# display.net
KiCad netlist of a schematic drawn in EAGLE
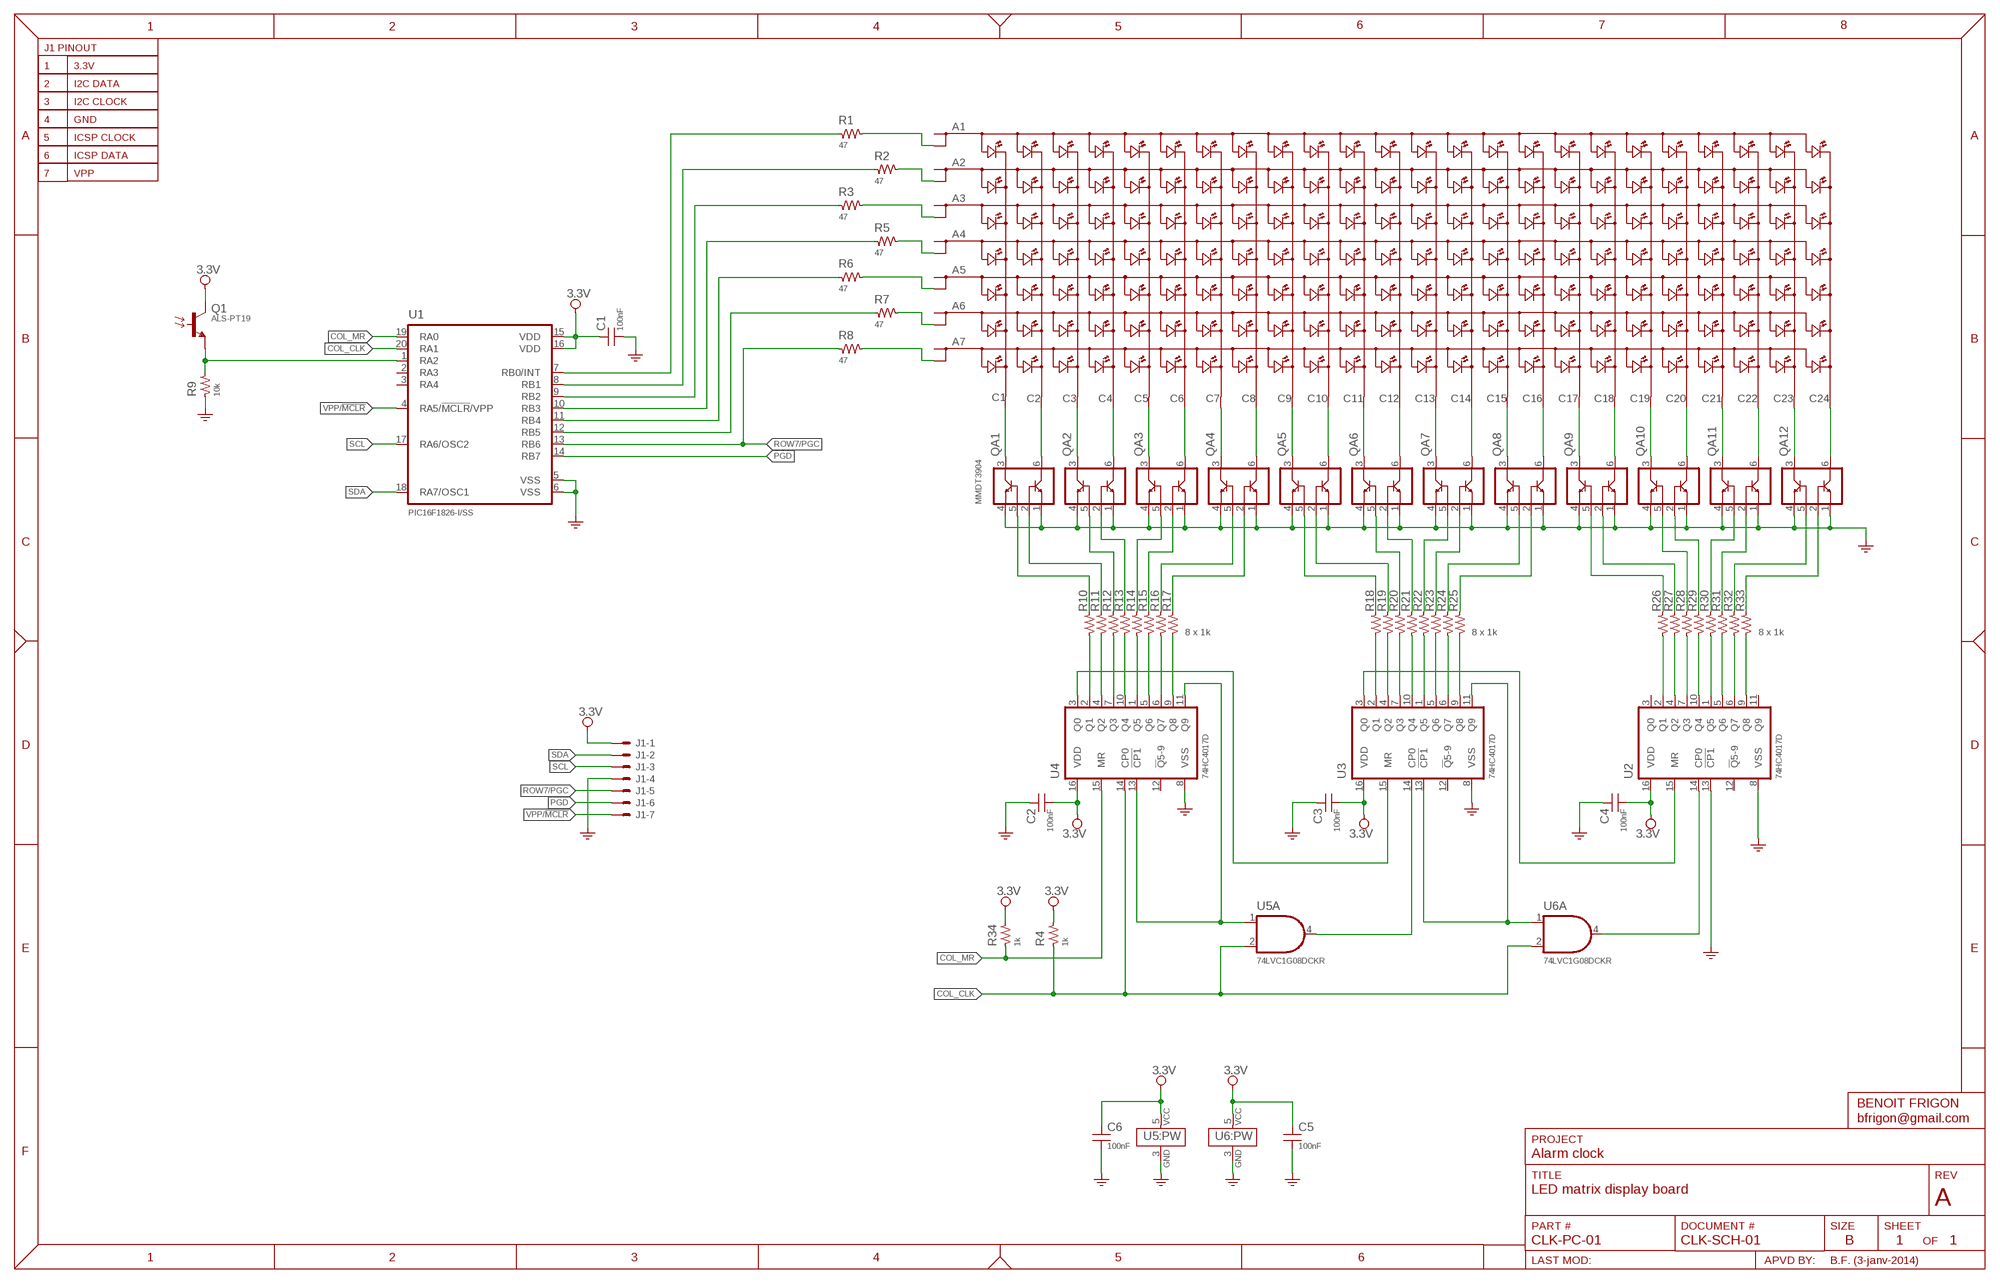
[diagram p0: schematic, sheet 1]

(export (version "E")
  (design (tool "Eeschema 10.0.6"))
  (components
    (comp (ref "C1")
      (value "100nF")
      (footprint "eagle-import:SMD_0603")
      (fields (field (name "PRICE") "0.00"))
      (libsource (lib "eagle-import") (part "CAP-0603"))
    )
    (comp (ref "C2")
      (value "100nF")
      (footprint "eagle-import:SMD_0603")
      (fields (field (name "PRICE") "0.00"))
      (libsource (lib "eagle-import") (part "CAP-0603"))
    )
    (comp (ref "C3")
      (value "100nF")
      (footprint "eagle-import:SMD_0603")
      (description "{DESCRIPTION} - SMT 0603 - {value}")
      (fields (field (name "PACKAGE") "SMT 0603") (field (name "PRICE") "0.00"))
      (libsource (lib "eagle-import") (part "CAP-0603"))
    )
    (comp (ref "C4")
      (value "100nF")
      (footprint "eagle-import:SMD_0603")
      (description "{DESCRIPTION} - SMT 0603 - {value}")
      (fields (field (name "PACKAGE") "SMT 0603") (field (name "PRICE") "0.00"))
      (libsource (lib "eagle-import") (part "CAP-0603"))
    )
    (comp (ref "C5")
      (value "100nF")
      (footprint "eagle-import:SMD_0603")
      (libsource (lib "eagle-import") (part "CAP-0603"))
    )
    (comp (ref "C6")
      (value "100nF")
      (footprint "eagle-import:SMD_0603")
      (libsource (lib "eagle-import") (part "CAP-0603"))
    )
    (comp (ref "J1")
      (value "SNG-2MM-HEADER-07-V")
      (footprint "eagle-import:DF3X-7P-2DSA")
      (fields
        (field (name "MFG") "Hirose Electronic")
        (field (name "PART_NO") "DF3A-7P-2DSA")
        (field (name "PRICE") "0.37")
        (field (name "SKU") "H2099-ND")
        (field (name "SUPPLIER") "Digi-Key")
      )
      (libsource (lib "eagle-import") (part "SNG-2MM-HEADER-07-V"))
    )
    (comp (ref "Q1")
      (value "ALS-PT19")
      (footprint "eagle-import:ALS-PT19")
      (fields
        (field (name "MFG") "Everlight")
        (field (name "PART_NO") "ALS-PT19-315C/L177/TR8")
        (field (name "PART_NO_1") "ALS-PT19-315C/L177/TR8")
      )
      (libsource (lib "eagle-import") (part "ALS-PT19"))
    )
    (comp (ref "QA1")
      (value "MMDT3904")
      (footprint "eagle-import:SOT363")
      (fields (field (name "MFG") "Diodes Inc."))
      (libsource (lib "eagle-import") (part "MMDT3904"))
    )
    (comp (ref "QA2")
      (value "MMDT3904")
      (footprint "eagle-import:SOT363")
      (fields (field (name "MFG") "Diodes Inc."))
      (libsource (lib "eagle-import") (part "MMDT3904"))
    )
    (comp (ref "QA3")
      (value "MMDT3904")
      (footprint "eagle-import:SOT363")
      (fields (field (name "MFG") "Diodes Inc."))
      (libsource (lib "eagle-import") (part "MMDT3904"))
    )
    (comp (ref "QA4")
      (value "MMDT3904")
      (footprint "eagle-import:SOT363")
      (fields (field (name "MFG") "Diodes Inc."))
      (libsource (lib "eagle-import") (part "MMDT3904"))
    )
    (comp (ref "QA5")
      (value "MMDT3904")
      (footprint "eagle-import:SOT363")
      (fields (field (name "MFG") "Diodes Inc."))
      (libsource (lib "eagle-import") (part "MMDT3904"))
    )
    (comp (ref "QA6")
      (value "MMDT3904")
      (footprint "eagle-import:SOT363")
      (fields (field (name "MFG") "Diodes Inc."))
      (libsource (lib "eagle-import") (part "MMDT3904"))
    )
    (comp (ref "QA7")
      (value "MMDT3904")
      (footprint "eagle-import:SOT363")
      (fields (field (name "MFG") "Diodes Inc."))
      (libsource (lib "eagle-import") (part "MMDT3904"))
    )
    (comp (ref "QA8")
      (value "MMDT3904")
      (footprint "eagle-import:SOT363")
      (fields (field (name "MFG") "Diodes Inc."))
      (libsource (lib "eagle-import") (part "MMDT3904"))
    )
    (comp (ref "QA9")
      (value "MMDT3904")
      (footprint "eagle-import:SOT363")
      (fields (field (name "MFG") "Diodes Inc."))
      (libsource (lib "eagle-import") (part "MMDT3904"))
    )
    (comp (ref "QA10")
      (value "MMDT3904")
      (footprint "eagle-import:SOT363")
      (fields (field (name "MFG") "Diodes Inc."))
      (libsource (lib "eagle-import") (part "MMDT3904"))
    )
    (comp (ref "QA11")
      (value "MMDT3904")
      (footprint "eagle-import:SOT363")
      (fields (field (name "MFG") "Diodes Inc."))
      (libsource (lib "eagle-import") (part "MMDT3904"))
    )
    (comp (ref "QA12")
      (value "MMDT3904")
      (footprint "eagle-import:SOT363")
      (fields (field (name "MFG") "Diodes Inc."))
      (libsource (lib "eagle-import") (part "MMDT3904"))
    )
    (comp (ref "R1")
      (value "47")
      (footprint "eagle-import:SMD_0603")
      (description "{DESCRIPTION} - SMT 0603 - {VALUE}")
      (fields (field (name "PACKAGE") "SMT 0603") (field (name "PRICE") "0.00"))
      (libsource (lib "eagle-import") (part "RES-0603"))
    )
    (comp (ref "R2")
      (value "47")
      (footprint "eagle-import:SMD_0603")
      (description "{DESCRIPTION} - SMT 0603 - {VALUE}")
      (fields (field (name "PACKAGE") "SMT 0603") (field (name "PRICE") "0.00"))
      (libsource (lib "eagle-import") (part "RES-0603"))
    )
    (comp (ref "R3")
      (value "47")
      (footprint "eagle-import:SMD_0603")
      (description "{DESCRIPTION} - SMT 0603 - {VALUE}")
      (fields (field (name "PACKAGE") "SMT 0603") (field (name "PRICE") "0.00"))
      (libsource (lib "eagle-import") (part "RES-0603"))
    )
    (comp (ref "R4")
      (value "1k")
      (footprint "eagle-import:SMD_0603")
      (fields (field (name "PRICE") "0.00"))
      (libsource (lib "eagle-import") (part "RES-0603"))
    )
    (comp (ref "R5")
      (value "47")
      (footprint "eagle-import:SMD_0603")
      (description "{DESCRIPTION} - SMT 0603 - {VALUE}")
      (fields (field (name "PACKAGE") "SMT 0603") (field (name "PRICE") "0.00"))
      (libsource (lib "eagle-import") (part "RES-0603"))
    )
    (comp (ref "R6")
      (value "47")
      (footprint "eagle-import:SMD_0603")
      (description "{DESCRIPTION} - SMT 0603 - {VALUE}")
      (fields (field (name "PACKAGE") "SMT 0603") (field (name "PRICE") "0.00"))
      (libsource (lib "eagle-import") (part "RES-0603"))
    )
    (comp (ref "R7")
      (value "47")
      (footprint "eagle-import:SMD_0603")
      (description "{DESCRIPTION} - SMT 0603 - {VALUE}")
      (fields (field (name "PACKAGE") "SMT 0603") (field (name "PRICE") "0.00"))
      (libsource (lib "eagle-import") (part "RES-0603"))
    )
    (comp (ref "R8")
      (value "47")
      (footprint "eagle-import:SMD_0603")
      (description "{DESCRIPTION} - SMT 0603 - {VALUE}")
      (fields (field (name "PACKAGE") "SMT 0603") (field (name "PRICE") "0.00"))
      (libsource (lib "eagle-import") (part "RES-0603"))
    )
    (comp (ref "R9")
      (value "10k")
      (footprint "eagle-import:SMD_0603")
      (libsource (lib "eagle-import") (part "RES-0603"))
    )
    (comp (ref "R10")
      (value "1k")
      (footprint "eagle-import:SMD_0603")
      (fields (field (name "PRICE") "0.00"))
      (libsource (lib "eagle-import") (part "RES-0603"))
    )
    (comp (ref "R11")
      (value "1k")
      (footprint "eagle-import:SMD_0603")
      (description "{DESCRIPTION} - SMT 0603 - {VALUE}")
      (fields (field (name "PACKAGE") "SMT 0603") (field (name "PRICE") "0.00"))
      (libsource (lib "eagle-import") (part "RES-0603"))
    )
    (comp (ref "R12")
      (value "1k")
      (footprint "eagle-import:SMD_0603")
      (description "{DESCRIPTION} - SMT 0603 - {VALUE}")
      (fields (field (name "PACKAGE") "SMT 0603") (field (name "PRICE") "0.00"))
      (libsource (lib "eagle-import") (part "RES-0603"))
    )
    (comp (ref "R13")
      (value "1k")
      (footprint "eagle-import:SMD_0603")
      (description "{DESCRIPTION} - SMT 0603 - {VALUE}")
      (fields (field (name "PACKAGE") "SMT 0603") (field (name "PRICE") "0.00"))
      (libsource (lib "eagle-import") (part "RES-0603"))
    )
    (comp (ref "R14")
      (value "1k")
      (footprint "eagle-import:SMD_0603")
      (description "{DESCRIPTION} - SMT 0603 - {VALUE}")
      (fields (field (name "PACKAGE") "SMT 0603") (field (name "PRICE") "0.00"))
      (libsource (lib "eagle-import") (part "RES-0603"))
    )
    (comp (ref "R15")
      (value "1k")
      (footprint "eagle-import:SMD_0603")
      (description "{DESCRIPTION} - SMT 0603 - {VALUE}")
      (fields (field (name "PACKAGE") "SMT 0603") (field (name "PRICE") "0.00"))
      (libsource (lib "eagle-import") (part "RES-0603"))
    )
    (comp (ref "R16")
      (value "1k")
      (footprint "eagle-import:SMD_0603")
      (description "{DESCRIPTION} - SMT 0603 - {VALUE}")
      (fields (field (name "PACKAGE") "SMT 0603") (field (name "PRICE") "0.00"))
      (libsource (lib "eagle-import") (part "RES-0603"))
    )
    (comp (ref "R17")
      (value "1k")
      (footprint "eagle-import:SMD_0603")
      (description "{DESCRIPTION} - SMT 0603 - {VALUE}")
      (fields (field (name "PACKAGE") "SMT 0603") (field (name "PRICE") "0.00"))
      (libsource (lib "eagle-import") (part "RES-0603"))
    )
    (comp (ref "R18")
      (value "1k")
      (footprint "eagle-import:SMD_0603")
      (description "{DESCRIPTION} - SMT 0603 - {VALUE}")
      (fields (field (name "PACKAGE") "SMT 0603") (field (name "PRICE") "0.00"))
      (libsource (lib "eagle-import") (part "RES-0603"))
    )
    (comp (ref "R19")
      (value "1k")
      (footprint "eagle-import:SMD_0603")
      (description "{DESCRIPTION} - SMT 0603 - {VALUE}")
      (fields (field (name "PACKAGE") "SMT 0603") (field (name "PRICE") "0.00"))
      (libsource (lib "eagle-import") (part "RES-0603"))
    )
    (comp (ref "R20")
      (value "1k")
      (footprint "eagle-import:SMD_0603")
      (description "{DESCRIPTION} - SMT 0603 - {VALUE}")
      (fields (field (name "PACKAGE") "SMT 0603") (field (name "PRICE") "0.00"))
      (libsource (lib "eagle-import") (part "RES-0603"))
    )
    (comp (ref "R21")
      (value "1k")
      (footprint "eagle-import:SMD_0603")
      (description "{DESCRIPTION} - SMT 0603 - {VALUE}")
      (fields (field (name "PACKAGE") "SMT 0603") (field (name "PRICE") "0.00"))
      (libsource (lib "eagle-import") (part "RES-0603"))
    )
    (comp (ref "R22")
      (value "1k")
      (footprint "eagle-import:SMD_0603")
      (description "{DESCRIPTION} - SMT 0603 - {VALUE}")
      (fields (field (name "PACKAGE") "SMT 0603") (field (name "PRICE") "0.00"))
      (libsource (lib "eagle-import") (part "RES-0603"))
    )
    (comp (ref "R23")
      (value "1k")
      (footprint "eagle-import:SMD_0603")
      (description "{DESCRIPTION} - SMT 0603 - {VALUE}")
      (fields (field (name "PACKAGE") "SMT 0603") (field (name "PRICE") "0.00"))
      (libsource (lib "eagle-import") (part "RES-0603"))
    )
    (comp (ref "R24")
      (value "1k")
      (footprint "eagle-import:SMD_0603")
      (description "{DESCRIPTION} - SMT 0603 - {VALUE}")
      (fields (field (name "PACKAGE") "SMT 0603") (field (name "PRICE") "0.00"))
      (libsource (lib "eagle-import") (part "RES-0603"))
    )
    (comp (ref "R25")
      (value "1k")
      (footprint "eagle-import:SMD_0603")
      (description "{DESCRIPTION} - SMT 0603 - {VALUE}")
      (fields (field (name "PACKAGE") "SMT 0603") (field (name "PRICE") "0.00"))
      (libsource (lib "eagle-import") (part "RES-0603"))
    )
    (comp (ref "R26")
      (value "1k")
      (footprint "eagle-import:SMD_0603")
      (description "{DESCRIPTION} - SMT 0603 - {VALUE}")
      (fields (field (name "PACKAGE") "SMT 0603") (field (name "PRICE") "0.00"))
      (libsource (lib "eagle-import") (part "RES-0603"))
    )
    (comp (ref "R27")
      (value "1k")
      (footprint "eagle-import:SMD_0603")
      (description "{DESCRIPTION} - SMT 0603 - {VALUE}")
      (fields (field (name "PACKAGE") "SMT 0603") (field (name "PRICE") "0.00"))
      (libsource (lib "eagle-import") (part "RES-0603"))
    )
    (comp (ref "R28")
      (value "1k")
      (footprint "eagle-import:SMD_0603")
      (description "{DESCRIPTION} - SMT 0603 - {VALUE}")
      (fields (field (name "PACKAGE") "SMT 0603") (field (name "PRICE") "0.00"))
      (libsource (lib "eagle-import") (part "RES-0603"))
    )
    (comp (ref "R29")
      (value "1k")
      (footprint "eagle-import:SMD_0603")
      (description "{DESCRIPTION} - SMT 0603 - {VALUE}")
      (fields (field (name "PACKAGE") "SMT 0603") (field (name "PRICE") "0.00"))
      (libsource (lib "eagle-import") (part "RES-0603"))
    )
    (comp (ref "R30")
      (value "1k")
      (footprint "eagle-import:SMD_0603")
      (description "{DESCRIPTION} - SMT 0603 - {VALUE}")
      (fields (field (name "PACKAGE") "SMT 0603") (field (name "PRICE") "0.00"))
      (libsource (lib "eagle-import") (part "RES-0603"))
    )
    (comp (ref "R31")
      (value "1k")
      (footprint "eagle-import:SMD_0603")
      (description "{DESCRIPTION} - SMT 0603 - {VALUE}")
      (fields (field (name "PACKAGE") "SMT 0603") (field (name "PRICE") "0.00"))
      (libsource (lib "eagle-import") (part "RES-0603"))
    )
    (comp (ref "R32")
      (value "1k")
      (footprint "eagle-import:SMD_0603")
      (description "{DESCRIPTION} - SMT 0603 - {VALUE}")
      (fields (field (name "PACKAGE") "SMT 0603") (field (name "PRICE") "0.00"))
      (libsource (lib "eagle-import") (part "RES-0603"))
    )
    (comp (ref "R33")
      (value "1k")
      (footprint "eagle-import:SMD_0603")
      (description "{DESCRIPTION} - SMT 0603 - {VALUE}")
      (fields (field (name "PACKAGE") "SMT 0603") (field (name "PRICE") "0.00"))
      (libsource (lib "eagle-import") (part "RES-0603"))
    )
    (comp (ref "R34")
      (value "1k")
      (footprint "eagle-import:SMD_0603")
      (fields (field (name "PRICE") "0.00"))
      (libsource (lib "eagle-import") (part "RES-0603"))
    )
    (comp (ref "U$1")
      (value "LED_MATRIX_V_24X7")
      (footprint "eagle-import:LED_MATRIX_V_24X7")
      (libsource (lib "eagle-import") (part "LED_MATRIX_V_24X7"))
    )
    (comp (ref "U1")
      (value "PIC16F1826-I/SS")
      (footprint "eagle-import:SSOP20")
      (fields (field (name "MFG") "Microchip"))
      (libsource (lib "eagle-import") (part "PIC16F1826-?I/SS"))
    )
    (comp (ref "U2")
      (value "74HC4017D")
      (footprint "eagle-import:SOIC16N")
      (fields (field (name "MFG") "NXP Semiconductors") (field (name "PART_NO") "74HC4017D,653"))
      (libsource (lib "eagle-import") (part "74HC4017D"))
    )
    (comp (ref "U3")
      (value "74HC4017D")
      (footprint "eagle-import:SOIC16N")
      (fields (field (name "MFG") "NXP Semiconductors") (field (name "PART_NO") "74HC4017D,653"))
      (libsource (lib "eagle-import") (part "74HC4017D"))
    )
    (comp (ref "U4")
      (value "74HC4017D")
      (footprint "eagle-import:SOIC16N")
      (fields (field (name "MFG") "NXP Semiconductors") (field (name "PART_NO") "74HC4017D,653"))
      (libsource (lib "eagle-import") (part "74HC4017D"))
    )
    (comp (ref "U5")
      (value "74LVC1G08DCKR")
      (footprint "eagle-import:SC70-5")
      (fields
        (field (name "MFG") "Texas Instruments")
        (field (name "MFG_1") "Texas Instruments")
        (field (name "PRICE") "0.29")
        (field (name "SKU") "296-11602-1-ND")
        (field (name "SUPPLIER") "Digi-Key")
      )
      (libsource (lib "eagle-import") (part "741G08DCKRLVC"))
    )
    (comp (ref "U6")
      (value "74LVC1G08DCKR")
      (footprint "eagle-import:SC70-5")
      (fields
        (field (name "MFG") "Texas Instruments")
        (field (name "MFG_1") "Texas Instruments")
        (field (name "PRICE") "0.29")
        (field (name "SKU") "296-11602-1-ND")
        (field (name "SUPPLIER") "Digi-Key")
      )
      (libsource (lib "eagle-import") (part "741G08DCKRLVC"))
    )
  )
  (nets
    (net (code "1") (name "/VPP{slash}~{MCLR}") (class "Default")
      (node (ref "J1") (pin "7") (pinfunction "S_7") (pintype "bidirectional"))
      (node (ref "U1") (pin "4") (pinfunction "RA5/~{MCLR}/VPP_4") (pintype "bidirectional"))
    )
    (net (code "2") (name "3.3V") (class "Default")
      (node (ref "C1") (pin "1") (pinfunction "1_1") (pintype "passive"))
      (node (ref "C2") (pin "2") (pinfunction "2_2") (pintype "passive"))
      (node (ref "C3") (pin "2") (pinfunction "2_2") (pintype "passive"))
      (node (ref "C4") (pin "2") (pinfunction "2_2") (pintype "passive"))
      (node (ref "C5") (pin "1") (pinfunction "1_1") (pintype "passive"))
      (node (ref "C6") (pin "1") (pinfunction "1_1") (pintype "passive"))
      (node (ref "J1") (pin "1") (pinfunction "S_1") (pintype "bidirectional"))
      (node (ref "Q1") (pin "C") (pinfunction "C_C") (pintype "passive"))
      (node (ref "R34") (pin "2") (pinfunction "2_2") (pintype "passive"))
      (node (ref "R4") (pin "2") (pinfunction "2_2") (pintype "passive"))
      (node (ref "U1") (pin "15") (pinfunction "VDD_15") (pintype "power_in"))
      (node (ref "U1") (pin "16") (pinfunction "VDD_16") (pintype "power_in"))
      (node (ref "U2") (pin "16") (pinfunction "VDD_16") (pintype "bidirectional"))
      (node (ref "U3") (pin "16") (pinfunction "VDD_16") (pintype "bidirectional"))
      (node (ref "U4") (pin "16") (pinfunction "VDD_16") (pintype "bidirectional"))
      (node (ref "U5") (pin "5") (pinfunction "VCC_5") (pintype "power_in"))
      (node (ref "U6") (pin "5") (pinfunction "VCC_5") (pintype "power_in"))
    )
    (net (code "3") (name "COL_CLK") (class "Default")
      (node (ref "R4") (pin "1") (pinfunction "1_1") (pintype "passive"))
      (node (ref "U1") (pin "20") (pinfunction "RA1_20") (pintype "bidirectional"))
      (node (ref "U4") (pin "14") (pinfunction "CP0_14") (pintype "bidirectional"))
      (node (ref "U5") (pin "2") (pinfunction "I1_2") (pintype "input"))
      (node (ref "U6") (pin "2") (pinfunction "I1_2") (pintype "input"))
    )
    (net (code "4") (name "COL_MR") (class "Default")
      (node (ref "R34") (pin "1") (pinfunction "1_1") (pintype "passive"))
      (node (ref "U1") (pin "19") (pinfunction "RA0_19") (pintype "bidirectional"))
      (node (ref "U4") (pin "15") (pinfunction "MR_15") (pintype "bidirectional"))
    )
    (net (code "5") (name "GND") (class "Default")
      (node (ref "C1") (pin "2") (pinfunction "2_2") (pintype "passive"))
      (node (ref "C2") (pin "1") (pinfunction "1_1") (pintype "passive"))
      (node (ref "C3") (pin "1") (pinfunction "1_1") (pintype "passive"))
      (node (ref "C4") (pin "1") (pinfunction "1_1") (pintype "passive"))
      (node (ref "C5") (pin "2") (pinfunction "2_2") (pintype "passive"))
      (node (ref "C6") (pin "2") (pinfunction "2_2") (pintype "passive"))
      (node (ref "J1") (pin "4") (pinfunction "S_4") (pintype "bidirectional"))
      (node (ref "QA1") (pin "1") (pinfunction "E2_1") (pintype "bidirectional"))
      (node (ref "QA1") (pin "4") (pinfunction "E1_4") (pintype "bidirectional"))
      (node (ref "QA10") (pin "1") (pinfunction "E2_1") (pintype "bidirectional"))
      (node (ref "QA10") (pin "4") (pinfunction "E1_4") (pintype "bidirectional"))
      (node (ref "QA11") (pin "1") (pinfunction "E2_1") (pintype "bidirectional"))
      (node (ref "QA11") (pin "4") (pinfunction "E1_4") (pintype "bidirectional"))
      (node (ref "QA12") (pin "1") (pinfunction "E2_1") (pintype "bidirectional"))
      (node (ref "QA12") (pin "4") (pinfunction "E1_4") (pintype "bidirectional"))
      (node (ref "QA2") (pin "1") (pinfunction "E2_1") (pintype "bidirectional"))
      (node (ref "QA2") (pin "4") (pinfunction "E1_4") (pintype "bidirectional"))
      (node (ref "QA3") (pin "1") (pinfunction "E2_1") (pintype "bidirectional"))
      (node (ref "QA3") (pin "4") (pinfunction "E1_4") (pintype "bidirectional"))
      (node (ref "QA4") (pin "1") (pinfunction "E2_1") (pintype "bidirectional"))
      (node (ref "QA4") (pin "4") (pinfunction "E1_4") (pintype "bidirectional"))
      (node (ref "QA5") (pin "1") (pinfunction "E2_1") (pintype "bidirectional"))
      (node (ref "QA5") (pin "4") (pinfunction "E1_4") (pintype "bidirectional"))
      (node (ref "QA6") (pin "1") (pinfunction "E2_1") (pintype "bidirectional"))
      (node (ref "QA6") (pin "4") (pinfunction "E1_4") (pintype "bidirectional"))
      (node (ref "QA7") (pin "1") (pinfunction "E2_1") (pintype "bidirectional"))
      (node (ref "QA7") (pin "4") (pinfunction "E1_4") (pintype "bidirectional"))
      (node (ref "QA8") (pin "1") (pinfunction "E2_1") (pintype "bidirectional"))
      (node (ref "QA8") (pin "4") (pinfunction "E1_4") (pintype "bidirectional"))
      (node (ref "QA9") (pin "1") (pinfunction "E2_1") (pintype "bidirectional"))
      (node (ref "QA9") (pin "4") (pinfunction "E1_4") (pintype "bidirectional"))
      (node (ref "R9") (pin "1") (pinfunction "1_1") (pintype "passive"))
      (node (ref "U1") (pin "5") (pinfunction "VSS_5") (pintype "power_in"))
      (node (ref "U1") (pin "6") (pinfunction "VSS_6") (pintype "power_in"))
      (node (ref "U2") (pin "13") (pinfunction "~{CP1}_13") (pintype "bidirectional"))
      (node (ref "U2") (pin "8") (pinfunction "VSS_8") (pintype "bidirectional"))
      (node (ref "U3") (pin "8") (pinfunction "VSS_8") (pintype "bidirectional"))
      (node (ref "U4") (pin "8") (pinfunction "VSS_8") (pintype "bidirectional"))
      (node (ref "U5") (pin "3") (pinfunction "GND_3") (pintype "power_in"))
      (node (ref "U6") (pin "3") (pinfunction "GND_3") (pintype "power_in"))
    )
    (net (code "6") (name "Net-(QA1-B1)") (class "Default")
      (node (ref "QA1") (pin "5") (pinfunction "B1_5") (pintype "bidirectional"))
      (node (ref "R10") (pin "2") (pinfunction "2_2") (pintype "passive"))
    )
    (net (code "7") (name "Net-(QA1-B2)") (class "Default")
      (node (ref "QA1") (pin "2") (pinfunction "B2_2") (pintype "bidirectional"))
      (node (ref "R11") (pin "2") (pinfunction "2_2") (pintype "passive"))
    )
    (net (code "8") (name "Net-(QA1-C1)") (class "Default")
      (node (ref "QA1") (pin "3") (pinfunction "C1_3") (pintype "bidirectional"))
      (node (ref "U$1") (pin "C1") (pinfunction "C1_C1") (pintype "bidirectional"))
    )
    (net (code "9") (name "Net-(QA1-C2)") (class "Default")
      (node (ref "QA1") (pin "6") (pinfunction "C2_6") (pintype "bidirectional"))
      (node (ref "U$1") (pin "C2") (pinfunction "C2_C2") (pintype "bidirectional"))
    )
    (net (code "10") (name "Net-(QA2-B1)") (class "Default")
      (node (ref "QA2") (pin "5") (pinfunction "B1_5") (pintype "bidirectional"))
      (node (ref "R12") (pin "2") (pinfunction "2_2") (pintype "passive"))
    )
    (net (code "11") (name "Net-(QA2-B2)") (class "Default")
      (node (ref "QA2") (pin "2") (pinfunction "B2_2") (pintype "bidirectional"))
      (node (ref "R13") (pin "2") (pinfunction "2_2") (pintype "passive"))
    )
    (net (code "12") (name "Net-(QA2-C1)") (class "Default")
      (node (ref "QA2") (pin "3") (pinfunction "C1_3") (pintype "bidirectional"))
      (node (ref "U$1") (pin "C3") (pinfunction "C3_C3") (pintype "bidirectional"))
    )
    (net (code "13") (name "Net-(QA2-C2)") (class "Default")
      (node (ref "QA2") (pin "6") (pinfunction "C2_6") (pintype "bidirectional"))
      (node (ref "U$1") (pin "C4") (pinfunction "C4_C4") (pintype "bidirectional"))
    )
    (net (code "14") (name "Net-(QA3-B1)") (class "Default")
      (node (ref "QA3") (pin "5") (pinfunction "B1_5") (pintype "bidirectional"))
      (node (ref "R14") (pin "2") (pinfunction "2_2") (pintype "passive"))
    )
    (net (code "15") (name "Net-(QA3-B2)") (class "Default")
      (node (ref "QA3") (pin "2") (pinfunction "B2_2") (pintype "bidirectional"))
      (node (ref "R15") (pin "2") (pinfunction "2_2") (pintype "passive"))
    )
    (net (code "16") (name "Net-(QA3-C1)") (class "Default")
      (node (ref "QA3") (pin "3") (pinfunction "C1_3") (pintype "bidirectional"))
      (node (ref "U$1") (pin "C5") (pinfunction "C5_C5") (pintype "bidirectional"))
    )
    (net (code "17") (name "Net-(QA3-C2)") (class "Default")
      (node (ref "QA3") (pin "6") (pinfunction "C2_6") (pintype "bidirectional"))
      (node (ref "U$1") (pin "C6") (pinfunction "C6_C6") (pintype "bidirectional"))
    )
    (net (code "18") (name "Net-(QA4-B1)") (class "Default")
      (node (ref "QA4") (pin "5") (pinfunction "B1_5") (pintype "bidirectional"))
      (node (ref "R16") (pin "2") (pinfunction "2_2") (pintype "passive"))
    )
    (net (code "19") (name "Net-(QA4-B2)") (class "Default")
      (node (ref "QA4") (pin "2") (pinfunction "B2_2") (pintype "bidirectional"))
      (node (ref "R17") (pin "2") (pinfunction "2_2") (pintype "passive"))
    )
    (net (code "20") (name "Net-(QA4-C1)") (class "Default")
      (node (ref "QA4") (pin "3") (pinfunction "C1_3") (pintype "bidirectional"))
      (node (ref "U$1") (pin "C7") (pinfunction "C7_C7") (pintype "bidirectional"))
    )
    (net (code "21") (name "Net-(QA4-C2)") (class "Default")
      (node (ref "QA4") (pin "6") (pinfunction "C2_6") (pintype "bidirectional"))
      (node (ref "U$1") (pin "C8") (pinfunction "C8_C8") (pintype "bidirectional"))
    )
    (net (code "22") (name "Net-(QA5-B1)") (class "Default")
      (node (ref "QA5") (pin "5") (pinfunction "B1_5") (pintype "bidirectional"))
      (node (ref "R18") (pin "2") (pinfunction "2_2") (pintype "passive"))
    )
    (net (code "23") (name "Net-(QA5-B2)") (class "Default")
      (node (ref "QA5") (pin "2") (pinfunction "B2_2") (pintype "bidirectional"))
      (node (ref "R19") (pin "2") (pinfunction "2_2") (pintype "passive"))
    )
    (net (code "24") (name "Net-(QA5-C1)") (class "Default")
      (node (ref "QA5") (pin "3") (pinfunction "C1_3") (pintype "bidirectional"))
      (node (ref "U$1") (pin "C9") (pinfunction "C9_C9") (pintype "bidirectional"))
    )
    (net (code "25") (name "Net-(QA5-C2)") (class "Default")
      (node (ref "QA5") (pin "6") (pinfunction "C2_6") (pintype "bidirectional"))
      (node (ref "U$1") (pin "C10") (pinfunction "C10_C10") (pintype "bidirectional"))
    )
    (net (code "26") (name "Net-(QA6-B1)") (class "Default")
      (node (ref "QA6") (pin "5") (pinfunction "B1_5") (pintype "bidirectional"))
      (node (ref "R20") (pin "2") (pinfunction "2_2") (pintype "passive"))
    )
    (net (code "27") (name "Net-(QA6-B2)") (class "Default")
      (node (ref "QA6") (pin "2") (pinfunction "B2_2") (pintype "bidirectional"))
      (node (ref "R21") (pin "2") (pinfunction "2_2") (pintype "passive"))
    )
    (net (code "28") (name "Net-(QA6-C1)") (class "Default")
      (node (ref "QA6") (pin "3") (pinfunction "C1_3") (pintype "bidirectional"))
      (node (ref "U$1") (pin "C11") (pinfunction "C11_C11") (pintype "bidirectional"))
    )
    (net (code "29") (name "Net-(QA6-C2)") (class "Default")
      (node (ref "QA6") (pin "6") (pinfunction "C2_6") (pintype "bidirectional"))
      (node (ref "U$1") (pin "C12") (pinfunction "C12_C12") (pintype "bidirectional"))
    )
    (net (code "30") (name "Net-(QA7-B1)") (class "Default")
      (node (ref "QA7") (pin "5") (pinfunction "B1_5") (pintype "bidirectional"))
      (node (ref "R22") (pin "2") (pinfunction "2_2") (pintype "passive"))
    )
    (net (code "31") (name "Net-(QA7-B2)") (class "Default")
      (node (ref "QA7") (pin "2") (pinfunction "B2_2") (pintype "bidirectional"))
      (node (ref "R23") (pin "2") (pinfunction "2_2") (pintype "passive"))
    )
    (net (code "32") (name "Net-(QA7-C1)") (class "Default")
      (node (ref "QA7") (pin "3") (pinfunction "C1_3") (pintype "bidirectional"))
      (node (ref "U$1") (pin "C13") (pinfunction "C13_C13") (pintype "bidirectional"))
    )
    (net (code "33") (name "Net-(QA7-C2)") (class "Default")
      (node (ref "QA7") (pin "6") (pinfunction "C2_6") (pintype "bidirectional"))
      (node (ref "U$1") (pin "C14") (pinfunction "C14_C14") (pintype "bidirectional"))
    )
    (net (code "34") (name "Net-(QA8-B1)") (class "Default")
      (node (ref "QA8") (pin "5") (pinfunction "B1_5") (pintype "bidirectional"))
      (node (ref "R24") (pin "2") (pinfunction "2_2") (pintype "passive"))
    )
    (net (code "35") (name "Net-(QA8-B2)") (class "Default")
      (node (ref "QA8") (pin "2") (pinfunction "B2_2") (pintype "bidirectional"))
      (node (ref "R25") (pin "2") (pinfunction "2_2") (pintype "passive"))
    )
    (net (code "36") (name "Net-(QA8-C1)") (class "Default")
      (node (ref "QA8") (pin "3") (pinfunction "C1_3") (pintype "bidirectional"))
      (node (ref "U$1") (pin "C15") (pinfunction "C15_C15") (pintype "bidirectional"))
    )
    (net (code "37") (name "Net-(QA8-C2)") (class "Default")
      (node (ref "QA8") (pin "6") (pinfunction "C2_6") (pintype "bidirectional"))
      (node (ref "U$1") (pin "C16") (pinfunction "C16_C16") (pintype "bidirectional"))
    )
    (net (code "38") (name "Net-(QA9-B1)") (class "Default")
      (node (ref "QA9") (pin "5") (pinfunction "B1_5") (pintype "bidirectional"))
      (node (ref "R26") (pin "2") (pinfunction "2_2") (pintype "passive"))
    )
    (net (code "39") (name "Net-(QA9-B2)") (class "Default")
      (node (ref "QA9") (pin "2") (pinfunction "B2_2") (pintype "bidirectional"))
      (node (ref "R27") (pin "2") (pinfunction "2_2") (pintype "passive"))
    )
    (net (code "40") (name "Net-(QA9-C1)") (class "Default")
      (node (ref "QA9") (pin "3") (pinfunction "C1_3") (pintype "bidirectional"))
      (node (ref "U$1") (pin "C17") (pinfunction "C17_C17") (pintype "bidirectional"))
    )
    (net (code "41") (name "Net-(QA9-C2)") (class "Default")
      (node (ref "QA9") (pin "6") (pinfunction "C2_6") (pintype "bidirectional"))
      (node (ref "U$1") (pin "C18") (pinfunction "C18_C18") (pintype "bidirectional"))
    )
    (net (code "42") (name "Net-(QA10-B1)") (class "Default")
      (node (ref "QA10") (pin "5") (pinfunction "B1_5") (pintype "bidirectional"))
      (node (ref "R28") (pin "2") (pinfunction "2_2") (pintype "passive"))
    )
    (net (code "43") (name "Net-(QA10-B2)") (class "Default")
      (node (ref "QA10") (pin "2") (pinfunction "B2_2") (pintype "bidirectional"))
      (node (ref "R29") (pin "2") (pinfunction "2_2") (pintype "passive"))
    )
    (net (code "44") (name "Net-(QA10-C1)") (class "Default")
      (node (ref "QA10") (pin "3") (pinfunction "C1_3") (pintype "bidirectional"))
      (node (ref "U$1") (pin "C19") (pinfunction "C19_C19") (pintype "bidirectional"))
    )
    (net (code "45") (name "Net-(QA10-C2)") (class "Default")
      (node (ref "QA10") (pin "6") (pinfunction "C2_6") (pintype "bidirectional"))
      (node (ref "U$1") (pin "C20") (pinfunction "C20_C20") (pintype "bidirectional"))
    )
    (net (code "46") (name "Net-(QA11-B1)") (class "Default")
      (node (ref "QA11") (pin "5") (pinfunction "B1_5") (pintype "bidirectional"))
      (node (ref "R30") (pin "2") (pinfunction "2_2") (pintype "passive"))
    )
    (net (code "47") (name "Net-(QA11-B2)") (class "Default")
      (node (ref "QA11") (pin "2") (pinfunction "B2_2") (pintype "bidirectional"))
      (node (ref "R31") (pin "2") (pinfunction "2_2") (pintype "passive"))
    )
    (net (code "48") (name "Net-(QA11-C1)") (class "Default")
      (node (ref "QA11") (pin "3") (pinfunction "C1_3") (pintype "bidirectional"))
      (node (ref "U$1") (pin "C21") (pinfunction "C21_C21") (pintype "bidirectional"))
    )
    (net (code "49") (name "Net-(QA11-C2)") (class "Default")
      (node (ref "QA11") (pin "6") (pinfunction "C2_6") (pintype "bidirectional"))
      (node (ref "U$1") (pin "C22") (pinfunction "C22_C22") (pintype "bidirectional"))
    )
    (net (code "50") (name "Net-(QA12-B1)") (class "Default")
      (node (ref "QA12") (pin "5") (pinfunction "B1_5") (pintype "bidirectional"))
      (node (ref "R32") (pin "2") (pinfunction "2_2") (pintype "passive"))
    )
    (net (code "51") (name "Net-(QA12-B2)") (class "Default")
      (node (ref "QA12") (pin "2") (pinfunction "B2_2") (pintype "bidirectional"))
      (node (ref "R33") (pin "2") (pinfunction "2_2") (pintype "passive"))
    )
    (net (code "52") (name "Net-(QA12-C1)") (class "Default")
      (node (ref "QA12") (pin "3") (pinfunction "C1_3") (pintype "bidirectional"))
      (node (ref "U$1") (pin "C23") (pinfunction "C23_C23") (pintype "bidirectional"))
    )
    (net (code "53") (name "Net-(QA12-C2)") (class "Default")
      (node (ref "QA12") (pin "6") (pinfunction "C2_6") (pintype "bidirectional"))
      (node (ref "U$1") (pin "C24") (pinfunction "C24_C24") (pintype "bidirectional"))
    )
    (net (code "54") (name "Net-(R1-Pad2)") (class "Default")
      (node (ref "R1") (pin "2") (pinfunction "2_2") (pintype "passive"))
      (node (ref "U$1") (pin "A1@2") (pinfunction "A1_A1@2") (pintype "bidirectional"))
    )
    (net (code "55") (name "Net-(R2-Pad2)") (class "Default")
      (node (ref "R2") (pin "2") (pinfunction "2_2") (pintype "passive"))
      (node (ref "U$1") (pin "A2@2") (pinfunction "A2_A2@2") (pintype "bidirectional"))
    )
    (net (code "56") (name "Net-(R3-Pad2)") (class "Default")
      (node (ref "R3") (pin "2") (pinfunction "2_2") (pintype "passive"))
      (node (ref "U$1") (pin "A3@2") (pinfunction "A3_A3@2") (pintype "bidirectional"))
    )
    (net (code "57") (name "Net-(R5-Pad2)") (class "Default")
      (node (ref "R5") (pin "2") (pinfunction "2_2") (pintype "passive"))
      (node (ref "U$1") (pin "A4@2") (pinfunction "A4_A4@2") (pintype "bidirectional"))
    )
    (net (code "58") (name "Net-(R6-Pad2)") (class "Default")
      (node (ref "R6") (pin "2") (pinfunction "2_2") (pintype "passive"))
      (node (ref "U$1") (pin "A5@2") (pinfunction "A5_A5@2") (pintype "bidirectional"))
    )
    (net (code "59") (name "Net-(R7-Pad2)") (class "Default")
      (node (ref "R7") (pin "2") (pinfunction "2_2") (pintype "passive"))
      (node (ref "U$1") (pin "A6@2") (pinfunction "A6_A6@2") (pintype "bidirectional"))
    )
    (net (code "60") (name "Net-(R8-Pad2)") (class "Default")
      (node (ref "R8") (pin "2") (pinfunction "2_2") (pintype "passive"))
      (node (ref "U$1") (pin "A7@2") (pinfunction "A7_A7@2") (pintype "bidirectional"))
    )
    (net (code "61") (name "Net-(U1-RA2)") (class "Default")
      (node (ref "Q1") (pin "E") (pinfunction "E_E") (pintype "passive"))
      (node (ref "R9") (pin "2") (pinfunction "2_2") (pintype "passive"))
      (node (ref "U1") (pin "1") (pinfunction "RA2_1") (pintype "bidirectional"))
    )
    (net (code "62") (name "Net-(U1-RB0{slash}INT)") (class "Default")
      (node (ref "R1") (pin "1") (pinfunction "1_1") (pintype "passive"))
      (node (ref "U1") (pin "7") (pinfunction "RB0/INT_7") (pintype "bidirectional"))
    )
    (net (code "63") (name "Net-(U1-RB1)") (class "Default")
      (node (ref "R2") (pin "1") (pinfunction "1_1") (pintype "passive"))
      (node (ref "U1") (pin "8") (pinfunction "RB1_8") (pintype "bidirectional"))
    )
    (net (code "64") (name "Net-(U1-RB2)") (class "Default")
      (node (ref "R3") (pin "1") (pinfunction "1_1") (pintype "passive"))
      (node (ref "U1") (pin "9") (pinfunction "RB2_9") (pintype "bidirectional"))
    )
    (net (code "65") (name "Net-(U1-RB3)") (class "Default")
      (node (ref "R5") (pin "1") (pinfunction "1_1") (pintype "passive"))
      (node (ref "U1") (pin "10") (pinfunction "RB3_10") (pintype "bidirectional"))
    )
    (net (code "66") (name "Net-(U1-RB4)") (class "Default")
      (node (ref "R6") (pin "1") (pinfunction "1_1") (pintype "passive"))
      (node (ref "U1") (pin "11") (pinfunction "RB4_11") (pintype "bidirectional"))
    )
    (net (code "67") (name "Net-(U1-RB5)") (class "Default")
      (node (ref "R7") (pin "1") (pinfunction "1_1") (pintype "passive"))
      (node (ref "U1") (pin "12") (pinfunction "RB5_12") (pintype "bidirectional"))
    )
    (net (code "68") (name "Net-(U2-CP0)") (class "Default")
      (node (ref "U2") (pin "14") (pinfunction "CP0_14") (pintype "bidirectional"))
      (node (ref "U6") (pin "4") (pinfunction "O_4") (pintype "output"))
    )
    (net (code "69") (name "Net-(U2-MR)") (class "Default")
      (node (ref "U2") (pin "15") (pinfunction "MR_15") (pintype "bidirectional"))
      (node (ref "U3") (pin "3") (pinfunction "Q0_3") (pintype "bidirectional"))
    )
    (net (code "70") (name "Net-(U2-Q1)") (class "Default")
      (node (ref "R26") (pin "1") (pinfunction "1_1") (pintype "passive"))
      (node (ref "U2") (pin "2") (pinfunction "Q1_2") (pintype "bidirectional"))
    )
    (net (code "71") (name "Net-(U2-Q2)") (class "Default")
      (node (ref "R27") (pin "1") (pinfunction "1_1") (pintype "passive"))
      (node (ref "U2") (pin "4") (pinfunction "Q2_4") (pintype "bidirectional"))
    )
    (net (code "72") (name "Net-(U2-Q3)") (class "Default")
      (node (ref "R28") (pin "1") (pinfunction "1_1") (pintype "passive"))
      (node (ref "U2") (pin "7") (pinfunction "Q3_7") (pintype "bidirectional"))
    )
    (net (code "73") (name "Net-(U2-Q4)") (class "Default")
      (node (ref "R29") (pin "1") (pinfunction "1_1") (pintype "passive"))
      (node (ref "U2") (pin "10") (pinfunction "Q4_10") (pintype "bidirectional"))
    )
    (net (code "74") (name "Net-(U2-Q5)") (class "Default")
      (node (ref "R30") (pin "1") (pinfunction "1_1") (pintype "passive"))
      (node (ref "U2") (pin "1") (pinfunction "Q5_1") (pintype "bidirectional"))
    )
    (net (code "75") (name "Net-(U2-Q6)") (class "Default")
      (node (ref "R31") (pin "1") (pinfunction "1_1") (pintype "passive"))
      (node (ref "U2") (pin "5") (pinfunction "Q6_5") (pintype "bidirectional"))
    )
    (net (code "76") (name "Net-(U2-Q7)") (class "Default")
      (node (ref "R32") (pin "1") (pinfunction "1_1") (pintype "passive"))
      (node (ref "U2") (pin "6") (pinfunction "Q7_6") (pintype "bidirectional"))
    )
    (net (code "77") (name "Net-(U2-Q8)") (class "Default")
      (node (ref "R33") (pin "1") (pinfunction "1_1") (pintype "passive"))
      (node (ref "U2") (pin "9") (pinfunction "Q8_9") (pintype "bidirectional"))
    )
    (net (code "78") (name "Net-(U3-CP0)") (class "Default")
      (node (ref "U3") (pin "14") (pinfunction "CP0_14") (pintype "bidirectional"))
      (node (ref "U5") (pin "4") (pinfunction "O_4") (pintype "output"))
    )
    (net (code "79") (name "Net-(U3-MR)") (class "Default")
      (node (ref "U3") (pin "15") (pinfunction "MR_15") (pintype "bidirectional"))
      (node (ref "U4") (pin "3") (pinfunction "Q0_3") (pintype "bidirectional"))
    )
    (net (code "80") (name "Net-(U3-Q1)") (class "Default")
      (node (ref "R18") (pin "1") (pinfunction "1_1") (pintype "passive"))
      (node (ref "U3") (pin "2") (pinfunction "Q1_2") (pintype "bidirectional"))
    )
    (net (code "81") (name "Net-(U3-Q2)") (class "Default")
      (node (ref "R19") (pin "1") (pinfunction "1_1") (pintype "passive"))
      (node (ref "U3") (pin "4") (pinfunction "Q2_4") (pintype "bidirectional"))
    )
    (net (code "82") (name "Net-(U3-Q3)") (class "Default")
      (node (ref "R20") (pin "1") (pinfunction "1_1") (pintype "passive"))
      (node (ref "U3") (pin "7") (pinfunction "Q3_7") (pintype "bidirectional"))
    )
    (net (code "83") (name "Net-(U3-Q4)") (class "Default")
      (node (ref "R21") (pin "1") (pinfunction "1_1") (pintype "passive"))
      (node (ref "U3") (pin "10") (pinfunction "Q4_10") (pintype "bidirectional"))
    )
    (net (code "84") (name "Net-(U3-Q5)") (class "Default")
      (node (ref "R22") (pin "1") (pinfunction "1_1") (pintype "passive"))
      (node (ref "U3") (pin "1") (pinfunction "Q5_1") (pintype "bidirectional"))
    )
    (net (code "85") (name "Net-(U3-Q6)") (class "Default")
      (node (ref "R23") (pin "1") (pinfunction "1_1") (pintype "passive"))
      (node (ref "U3") (pin "5") (pinfunction "Q6_5") (pintype "bidirectional"))
    )
    (net (code "86") (name "Net-(U3-Q7)") (class "Default")
      (node (ref "R24") (pin "1") (pinfunction "1_1") (pintype "passive"))
      (node (ref "U3") (pin "6") (pinfunction "Q7_6") (pintype "bidirectional"))
    )
    (net (code "87") (name "Net-(U3-Q8)") (class "Default")
      (node (ref "R25") (pin "1") (pinfunction "1_1") (pintype "passive"))
      (node (ref "U3") (pin "9") (pinfunction "Q8_9") (pintype "bidirectional"))
    )
    (net (code "88") (name "Net-(U3-Q9)") (class "Default")
      (node (ref "U3") (pin "11") (pinfunction "Q9_11") (pintype "bidirectional"))
      (node (ref "U3") (pin "13") (pinfunction "~{CP1}_13") (pintype "bidirectional"))
      (node (ref "U6") (pin "1") (pinfunction "I0_1") (pintype "input"))
    )
    (net (code "89") (name "Net-(U4-Q1)") (class "Default")
      (node (ref "R10") (pin "1") (pinfunction "1_1") (pintype "passive"))
      (node (ref "U4") (pin "2") (pinfunction "Q1_2") (pintype "bidirectional"))
    )
    (net (code "90") (name "Net-(U4-Q2)") (class "Default")
      (node (ref "R11") (pin "1") (pinfunction "1_1") (pintype "passive"))
      (node (ref "U4") (pin "4") (pinfunction "Q2_4") (pintype "bidirectional"))
    )
    (net (code "91") (name "Net-(U4-Q3)") (class "Default")
      (node (ref "R12") (pin "1") (pinfunction "1_1") (pintype "passive"))
      (node (ref "U4") (pin "7") (pinfunction "Q3_7") (pintype "bidirectional"))
    )
    (net (code "92") (name "Net-(U4-Q4)") (class "Default")
      (node (ref "R13") (pin "1") (pinfunction "1_1") (pintype "passive"))
      (node (ref "U4") (pin "10") (pinfunction "Q4_10") (pintype "bidirectional"))
    )
    (net (code "93") (name "Net-(U4-Q5)") (class "Default")
      (node (ref "R14") (pin "1") (pinfunction "1_1") (pintype "passive"))
      (node (ref "U4") (pin "1") (pinfunction "Q5_1") (pintype "bidirectional"))
    )
    (net (code "94") (name "Net-(U4-Q6)") (class "Default")
      (node (ref "R15") (pin "1") (pinfunction "1_1") (pintype "passive"))
      (node (ref "U4") (pin "5") (pinfunction "Q6_5") (pintype "bidirectional"))
    )
    (net (code "95") (name "Net-(U4-Q7)") (class "Default")
      (node (ref "R16") (pin "1") (pinfunction "1_1") (pintype "passive"))
      (node (ref "U4") (pin "6") (pinfunction "Q7_6") (pintype "bidirectional"))
    )
    (net (code "96") (name "Net-(U4-Q8)") (class "Default")
      (node (ref "R17") (pin "1") (pinfunction "1_1") (pintype "passive"))
      (node (ref "U4") (pin "9") (pinfunction "Q8_9") (pintype "bidirectional"))
    )
    (net (code "97") (name "Net-(U4-Q9)") (class "Default")
      (node (ref "U4") (pin "11") (pinfunction "Q9_11") (pintype "bidirectional"))
      (node (ref "U4") (pin "13") (pinfunction "~{CP1}_13") (pintype "bidirectional"))
      (node (ref "U5") (pin "1") (pinfunction "I0_1") (pintype "input"))
    )
    (net (code "98") (name "PGD") (class "Default")
      (node (ref "J1") (pin "6") (pinfunction "S_6") (pintype "bidirectional"))
      (node (ref "U1") (pin "14") (pinfunction "RB7_14") (pintype "bidirectional"))
    )
    (net (code "99") (name "ROW7{slash}PGC") (class "Default")
      (node (ref "J1") (pin "5") (pinfunction "S_5") (pintype "bidirectional"))
      (node (ref "R8") (pin "1") (pinfunction "1_1") (pintype "passive"))
      (node (ref "U1") (pin "13") (pinfunction "RB6_13") (pintype "bidirectional"))
    )
    (net (code "100") (name "SCL") (class "Default")
      (node (ref "J1") (pin "3") (pinfunction "S_3") (pintype "bidirectional"))
      (node (ref "U1") (pin "17") (pinfunction "RA6/OSC2_17") (pintype "bidirectional"))
    )
    (net (code "101") (name "SDA") (class "Default")
      (node (ref "J1") (pin "2") (pinfunction "S_2") (pintype "bidirectional"))
      (node (ref "U1") (pin "18") (pinfunction "RA7/OSC1_18") (pintype "bidirectional"))
    )
    (net (code "102") (name "unconnected-(U$1-A1-PadA1@1)") (class "Default")
      (node (ref "U$1") (pin "A1@1") (pinfunction "A1_A1@1") (pintype "bidirectional"))
    )
    (net (code "103") (name "unconnected-(U$1-A2-PadA2@1)") (class "Default")
      (node (ref "U$1") (pin "A2@1") (pinfunction "A2_A2@1") (pintype "bidirectional"))
    )
    (net (code "104") (name "unconnected-(U$1-A3-PadA3@1)") (class "Default")
      (node (ref "U$1") (pin "A3@1") (pinfunction "A3_A3@1") (pintype "bidirectional"))
    )
    (net (code "105") (name "unconnected-(U$1-A4-PadA4@1)") (class "Default")
      (node (ref "U$1") (pin "A4@1") (pinfunction "A4_A4@1") (pintype "bidirectional"))
    )
    (net (code "106") (name "unconnected-(U$1-A5-PadA5@1)") (class "Default")
      (node (ref "U$1") (pin "A5@1") (pinfunction "A5_A5@1") (pintype "bidirectional"))
    )
    (net (code "107") (name "unconnected-(U$1-A6-PadA6@1)") (class "Default")
      (node (ref "U$1") (pin "A6@1") (pinfunction "A6_A6@1") (pintype "bidirectional"))
    )
    (net (code "108") (name "unconnected-(U$1-A7-PadA7@1)") (class "Default")
      (node (ref "U$1") (pin "A7@1") (pinfunction "A7_A7@1") (pintype "bidirectional"))
    )
    (net (code "109") (name "unconnected-(U1-RA3-Pad2)") (class "Default")
      (node (ref "U1") (pin "2") (pinfunction "RA3_2") (pintype "bidirectional"))
    )
    (net (code "110") (name "unconnected-(U1-RA4-Pad3)") (class "Default")
      (node (ref "U1") (pin "3") (pinfunction "RA4_3") (pintype "bidirectional"))
    )
    (net (code "111") (name "unconnected-(U2-Q0-Pad3)") (class "Default")
      (node (ref "U2") (pin "3") (pinfunction "Q0_3") (pintype "bidirectional"))
    )
    (net (code "112") (name "unconnected-(U2-Q9-Pad11)") (class "Default")
      (node (ref "U2") (pin "11") (pinfunction "Q9_11") (pintype "bidirectional"))
    )
    (net (code "113") (name "unconnected-(U2-~{Q}5-9-Pad12)") (class "Default")
      (node (ref "U2") (pin "12") (pinfunction "~{Q}5-9_12") (pintype "bidirectional"))
    )
    (net (code "114") (name "unconnected-(U3-~{Q}5-9-Pad12)") (class "Default")
      (node (ref "U3") (pin "12") (pinfunction "~{Q}5-9_12") (pintype "bidirectional"))
    )
    (net (code "115") (name "unconnected-(U4-~{Q}5-9-Pad12)") (class "Default")
      (node (ref "U4") (pin "12") (pinfunction "~{Q}5-9_12") (pintype "bidirectional"))
    )
  )
)
